# WARG_EE_Bootcamp.net
KiCad netlist of a schematic drawn in Altium Designer
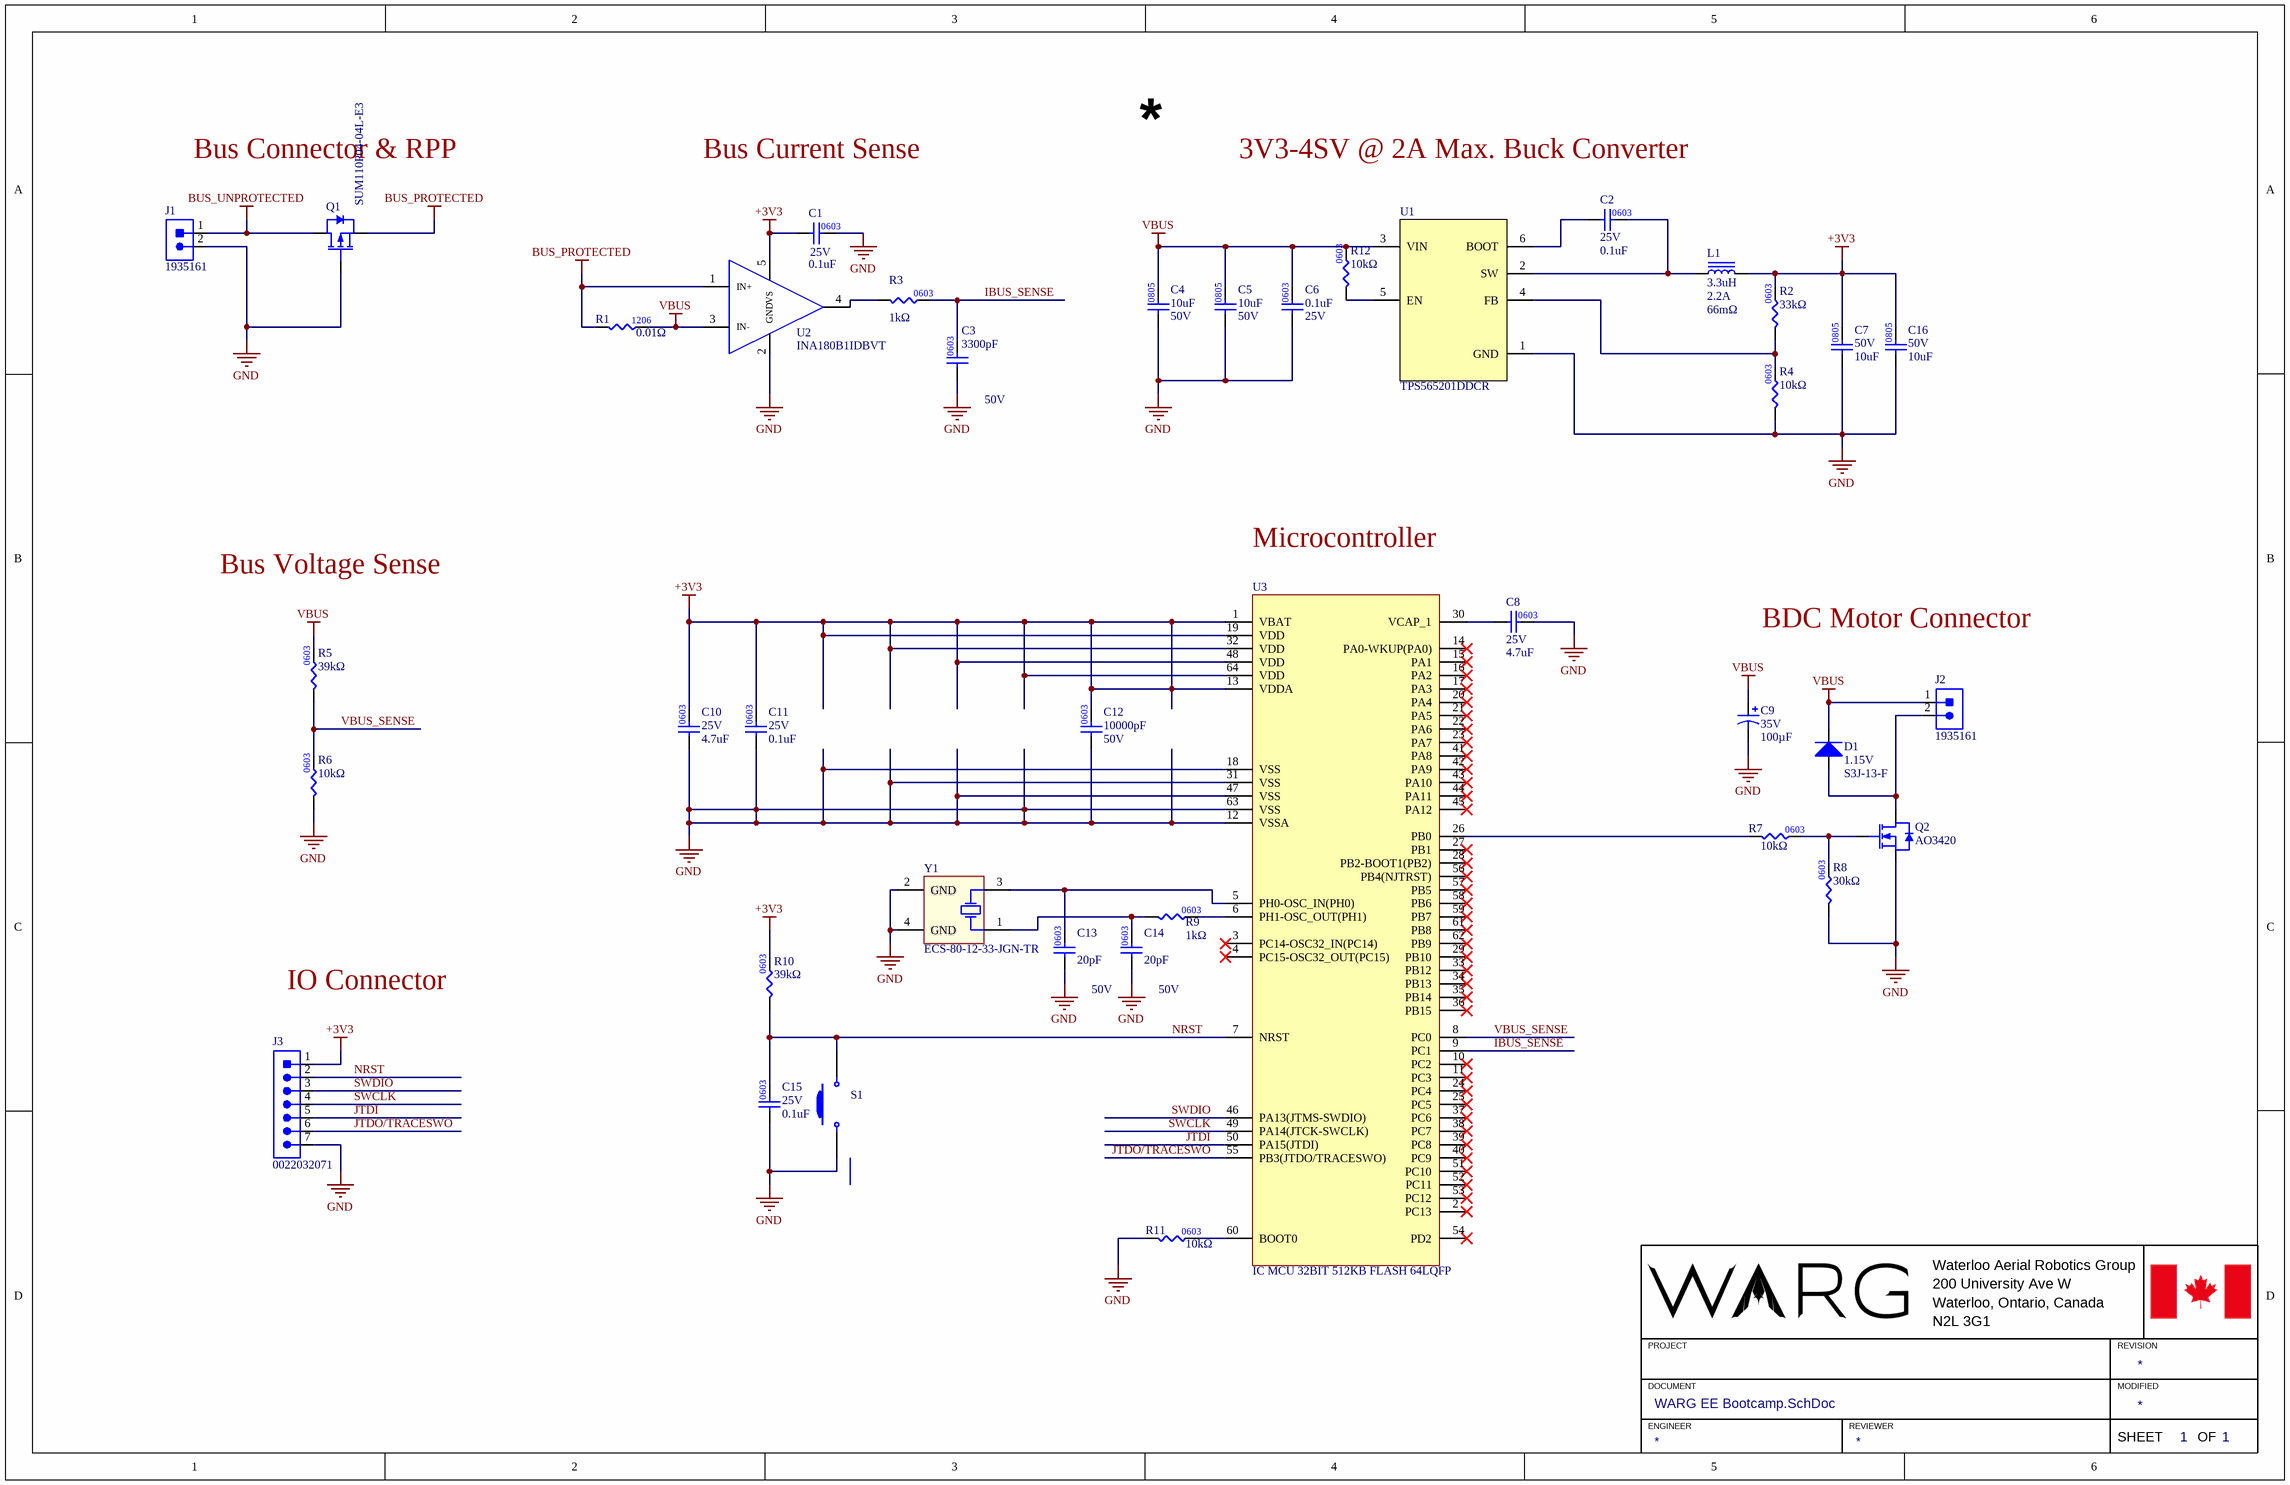
[diagram p0: WARG EE Bootcamp.SchDoc]

(export (version "E")
  (design (tool "Eeschema 10.0.6"))
  (components
    (comp (ref "C1")
      (value "0.1uF")
      (footprint "CAP0603")
      (description "CAP CER 0.1UF 25V X7R ±10% 0603")
      (fields (field (name "TOLERANCE") "±10%") (field (name "VOLTAGE") "25V"))
      (libsource (lib "Bootcamp SchLib") (part "GCM188R71E104KA57D"))
    )
    (comp (ref "C2")
      (value "0.1uF")
      (footprint "CAP0603")
      (description "CAP CER 0.1UF 25V X7R ±10% 0603")
      (fields (field (name "TOLERANCE") "±10%") (field (name "VOLTAGE") "25V"))
      (libsource (lib "Bootcamp SchLib") (part "GCM188R71E104KA57D"))
    )
    (comp (ref "C3")
      (value "3300pF")
      (footprint "CAP0603")
      (description "CAP CER 3300PF 50V C0G/NP0 0603")
      (fields (field (name "TOLERANCE") "±5%") (field (name "VOLTAGE RATING") "50V"))
      (libsource (lib "Bootcamp SchLib") (part "GRM1885C1H332JA01D"))
    )
    (comp (ref "C4")
      (value "10uF")
      (footprint "CAP0805")
      (description "CAP CER 10UF 50V X5R ±10% 0805")
      (fields (field (name "TOLERANCE") "±10%") (field (name "VOLTAGE") "50V"))
      (libsource (lib "Bootcamp SchLib") (part "GRM21BR61H106KE43L"))
    )
    (comp (ref "C5")
      (value "10uF")
      (footprint "CAP0805")
      (description "CAP CER 10UF 50V X5R ±10% 0805")
      (fields (field (name "TOLERANCE") "±10%") (field (name "VOLTAGE") "50V"))
      (libsource (lib "Bootcamp SchLib") (part "GRM21BR61H106KE43L"))
    )
    (comp (ref "C6")
      (value "0.1uF")
      (footprint "CAP0603")
      (description "CAP CER 0.1UF 25V X7R ±10% 0603")
      (fields (field (name "TOLERANCE") "±10%") (field (name "VOLTAGE") "25V"))
      (libsource (lib "Bootcamp SchLib") (part "GCM188R71E104KA57D"))
    )
    (comp (ref "C7")
      (value "10uF")
      (footprint "CAP0805")
      (description "CAP CER 10UF 50V X5R ±10% 0805")
      (fields (field (name "TOLERANCE") "±10%") (field (name "VOLTAGE") "50V"))
      (libsource (lib "Bootcamp SchLib") (part "GRM21BR61H106KE43L"))
    )
    (comp (ref "C8")
      (value "4.7uF")
      (footprint "CAP0603")
      (description "CAP CER 4.7UF 25V X6S ±10% 0603")
      (fields (field (name "TOLERANCE") "±10%") (field (name "VOLTAGE") "25V"))
      (libsource (lib "Bootcamp SchLib") (part "GRM188C81E475KE11D"))
    )
    (comp (ref "C9")
      (value "100µF")
      (footprint "RADIAL_CORNELL_D")
      (description "CAP ALUM 100UF 20% 35V SMD")
      (fields (field (name "TOLERANCE") "±20%") (field (name "VOLTAGE RATING") "35V"))
      (libsource (lib "Bootcamp SchLib") (part "35TKV100M8X10.5"))
    )
    (comp (ref "C10")
      (value "4.7uF")
      (footprint "CAP0603")
      (description "CAP CER 4.7UF 25V X6S ±10% 0603")
      (fields (field (name "TOLERANCE") "±10%") (field (name "VOLTAGE") "25V"))
      (libsource (lib "Bootcamp SchLib") (part "GRM188C81E475KE11D"))
    )
    (comp (ref "C11")
      (value "0.1uF")
      (footprint "CAP0603")
      (description "CAP CER 0.1UF 25V X7R ±10% 0603")
      (fields (field (name "TOLERANCE") "±10%") (field (name "VOLTAGE") "25V"))
      (libsource (lib "Bootcamp SchLib") (part "GCM188R71E104KA57D"))
    )
    (comp (ref "C12")
      (value "10000pF")
      (footprint "CAP0603")
      (description "CAP CER 10000PF 50V X7R 0603")
      (fields (field (name "TOLERANCE") "±5%") (field (name "VOLTAGE RATING") "50V"))
      (libsource (lib "Bootcamp SchLib") (part "C0603C103J5RAC7867"))
    )
    (comp (ref "C13")
      (value "20pF")
      (footprint "CAP0603")
      (description "CAP CER 20PF 50V C0G/NP0 0201")
      (fields (field (name "TOLERANCE") "±5%") (field (name "VOLTAGE RATING") "50V"))
      (libsource (lib "Bootcamp SchLib") (part "GRM0335C1H200GA01D"))
    )
    (comp (ref "C14")
      (value "20pF")
      (footprint "CAP0603")
      (description "CAP CER 20PF 50V C0G/NP0 0201")
      (fields (field (name "TOLERANCE") "±5%") (field (name "VOLTAGE RATING") "50V"))
      (libsource (lib "Bootcamp SchLib") (part "GRM0335C1H200GA01D"))
    )
    (comp (ref "C15")
      (value "0.1uF")
      (footprint "CAP0603")
      (description "CAP CER 0.1UF 25V X7R ±10% 0603")
      (fields (field (name "TOLERANCE") "±10%") (field (name "VOLTAGE") "25V"))
      (libsource (lib "Bootcamp SchLib") (part "GCM188R71E104KA57D"))
    )
    (comp (ref "C16")
      (value "10uF")
      (footprint "CAP0805")
      (description "CAP CER 10UF 50V X5R ±10% 0805")
      (fields (field (name "TOLERANCE") "±10%") (field (name "VOLTAGE") "50V"))
      (libsource (lib "Bootcamp SchLib") (part "GRM21BR61H106KE43L"))
    )
    (comp (ref "D1")
      (value "DIODE GEN PURP 600V 3A SMC")
      (footprint "SMC")
      (fields (field (name "FORWARD VOLTAGE") "1.15V") (field (name "MANUFACTURER PART NUMBER 1") "S3J-13-F"))
      (libsource (lib "Bootcamp SchLib") (part "S3J-FDICT-ND"))
    )
    (comp (ref "J1")
      (value "CON_2POS_SCREW_TERM")
      (footprint "1935161")
      (description "CONN SCREW TERMINAL 2X1 5MM RA TH")
      (fields (field (name "MANUFACTURER PART NUMBER 1") "1935161"))
      (libsource (lib "") (part "1935161_1"))
    )
    (comp (ref "J2")
      (value "CON_2POS_SCREW_TERM")
      (footprint "1935161")
      (description "CONN SCREW TERMINAL 2X1 5MM RA TH")
      (fields (field (name "MANUFACTURER PART NUMBER 1") "1935161"))
      (libsource (lib "Bootcamp SchLib") (part "1935161"))
    )
    (comp (ref "J3")
      (value "CONN HEADER VERT 7POS 2.54MM")
      (footprint "0022284070")
      (fields (field (name "MANUFACTURER PART NUMBER 1") "0022032071"))
      (libsource (lib "Bootcamp SchLib") (part "0022032071"))
    )
    (comp (ref "L1")
      (value "3.3uH")
      (description "FIXED IND 2.2UH 2.9A 44 MOHM SMD")
      (fields (field (name "CURRENT RATING") "2.2A") (field (name "DC RESISTANCE") "66mΩ"))
      (libsource (lib "Bootcamp SchLib") (part "SRN4018-2R2M"))
    )
    (comp (ref "Q1")
      (value "SUM110P04-04L-E3")
      (footprint "TO-263 (D²Pak)")
      (libsource (lib "Bootcamp SchLib") (part "SUM110P04-04L-E3"))
    )
    (comp (ref "Q2")
      (value "MOSFET N-CH 20V 6A SOT23-3L")
      (footprint "SOT23-3")
      (fields (field (name "MANUFACTURER PART NUMBER 1") "AO3420"))
      (libsource (lib "Bootcamp SchLib") (part "AO3420"))
    )
    (comp (ref "R1")
      (value "0.01Ω")
      (footprint "RES1206")
      (description "RES 0.01 OHM 1% 1/4W 1206")
      (fields (field (name "TOLERANCE") "±1%"))
      (libsource (lib "Bootcamp SchLib") (part "PF1206FRF070R01L"))
    )
    (comp (ref "R2")
      (value "33kΩ")
      (footprint "RES0603")
      (description "RES 33K OHM 1% 1/10W 0603")
      (fields (field (name "TOLERANCE") "±1%"))
      (libsource (lib "Bootcamp SchLib") (part "RC0603FR-0733KL"))
    )
    (comp (ref "R3")
      (value "1kΩ")
      (footprint "RES0603")
      (description "RES 1K OHM 1% 1/10W 0603")
      (fields (field (name "TOLERANCE") "±1%"))
      (libsource (lib "Bootcamp SchLib") (part "RC0603FR-071KL"))
    )
    (comp (ref "R4")
      (value "10kΩ")
      (footprint "RES0603")
      (description "RES 10K OHM 1% 1/10W 0603")
      (fields (field (name "TOLERANCE") "±1%"))
      (libsource (lib "Bootcamp SchLib") (part "RC0603FR-0710KL"))
    )
    (comp (ref "R5")
      (value "39kΩ")
      (footprint "RES0603")
      (description "RES 39K OHM 1% 1/10W 0603")
      (fields (field (name "TOLERANCE") "±1%"))
      (libsource (lib "Bootcamp SchLib") (part "RC0603FR-0739KL"))
    )
    (comp (ref "R6")
      (value "10kΩ")
      (footprint "RES0603")
      (description "RES 10K OHM 1% 1/10W 0603")
      (fields (field (name "TOLERANCE") "±1%"))
      (libsource (lib "Bootcamp SchLib") (part "RC0603FR-0710KL"))
    )
    (comp (ref "R7")
      (value "10kΩ")
      (footprint "RES0603")
      (description "RES 10K OHM 1% 1/10W 0603")
      (fields (field (name "TOLERANCE") "±1%"))
      (libsource (lib "Bootcamp SchLib") (part "RC0603FR-0710KL"))
    )
    (comp (ref "R8")
      (value "30kΩ")
      (footprint "RES0603")
      (description "RES 30K OHM 1% 1/10W 0603")
      (fields (field (name "TOLERANCE") "±1%"))
      (libsource (lib "Bootcamp SchLib") (part "RC0603FR-0730KL"))
    )
    (comp (ref "R9")
      (value "1kΩ")
      (footprint "RES0603")
      (description "RES 1K OHM 1% 1/10W 0603")
      (fields (field (name "TOLERANCE") "±1%"))
      (libsource (lib "Bootcamp SchLib") (part "RC0603FR-071KL"))
    )
    (comp (ref "R10")
      (value "39kΩ")
      (footprint "RES0603")
      (description "RES 39K OHM 1% 1/10W 0603")
      (fields (field (name "TOLERANCE") "±1%"))
      (libsource (lib "Bootcamp SchLib") (part "RC0603FR-0739KL"))
    )
    (comp (ref "R11")
      (value "10kΩ")
      (footprint "RES0603")
      (description "RES 10K OHM 1% 1/10W 0603")
      (fields (field (name "TOLERANCE") "±1%"))
      (libsource (lib "Bootcamp SchLib") (part "RC0603FR-0710KL"))
    )
    (comp (ref "R12")
      (value "10kΩ")
      (footprint "RES0603")
      (description "RES 10K OHM 1% 1/10W 0603")
      (fields (field (name "TOLERANCE") "±1%"))
      (libsource (lib "Bootcamp SchLib") (part "RC0603FR-0710KL"))
    )
    (comp (ref "S1")
      (value "435151014824")
      (footprint "435151014824")
      (description "SMT 3.0 X 2.6 MM TACT SWITCH WIT")
      (libsource (lib "Bootcamp SchLib") (part "435151014824"))
    )
    (comp (ref "U1")
      (value "IC REG BUCK ADJ 5A TSOT23-6")
      (footprint "SOT23-6")
      (fields (field (name "MANUFACTURER PART NUMBER 1") "TPS565201DDCR"))
      (libsource (lib "Bootcamp SchLib") (part "TPS565201DDCR"))
    )
    (comp (ref "U2")
      (value "IC CURR SENSE 1 CIRCUIT SOT23-5")
      (footprint "SOT23-5")
      (fields (field (name "MANUFACTURER PART NUMBER 1") "INA180B1IDBVT"))
      (libsource (lib "Bootcamp SchLib") (part "INA180B1IDBVT"))
    )
    (comp (ref "U3")
      (value "IC MCU 32BIT 512KB FLASH 64LQFP")
      (footprint "STM_LQFP64_N")
      (libsource (lib "Bootcamp SchLib") (part "STM32F446RET6"))
    )
    (comp (ref "Y1")
      (value "CRYSTAL 8MHZ 12PF SMD")
      (description "8 MHz ±20ppm Crystal 12pF 400 Ohms 4-SMD")
      (fields (field (name "MANUFACTURER PART NUMBER 1") "ECS-80-12-33-JGN-TR"))
      (libsource (lib "Bootcamp SchLib") (part "ECS-80-12-33-JGN-TR"))
    )
  )
  (nets
    (net (code "1") (name "+3V3") (class "Default")
      (node (ref "C1") (pin "1") (pinfunction "1_1") (pintype "passive"))
      (node (ref "C10") (pin "2") (pinfunction "2_2") (pintype "passive"))
      (node (ref "C11") (pin "2") (pinfunction "2_2") (pintype "passive"))
      (node (ref "C12") (pin "2") (pinfunction "2_2") (pintype "passive"))
      (node (ref "C16") (pin "2") (pinfunction "2_2") (pintype "passive"))
      (node (ref "C7") (pin "2") (pinfunction "2_2") (pintype "passive"))
      (node (ref "J3") (pin "1") (pinfunction "1_1") (pintype "passive"))
      (node (ref "L1") (pin "2") (pinfunction "2_2") (pintype "passive"))
      (node (ref "R10") (pin "2") (pinfunction "2_2") (pintype "passive"))
      (node (ref "R2") (pin "2") (pinfunction "2_2") (pintype "passive"))
      (node (ref "U2") (pin "5") (pinfunction "VS_5") (pintype "power_in"))
      (node (ref "U3") (pin "1") (pinfunction "VBAT_1") (pintype "passive"))
      (node (ref "U3") (pin "13") (pinfunction "VDDA_13") (pintype "passive"))
      (node (ref "U3") (pin "19") (pinfunction "VDD_19") (pintype "passive"))
      (node (ref "U3") (pin "32") (pinfunction "VDD_32") (pintype "passive"))
      (node (ref "U3") (pin "48") (pinfunction "VDD_48") (pintype "passive"))
      (node (ref "U3") (pin "64") (pinfunction "VDD_64") (pintype "passive"))
    )
    (net (code "2") (name "/IBUS_SENSE") (class "Default")
      (node (ref "C3") (pin "2") (pinfunction "2_2") (pintype "passive"))
      (node (ref "R3") (pin "2") (pinfunction "2_2") (pintype "passive"))
      (node (ref "U3") (pin "9") (pinfunction "PC1_9") (pintype "passive"))
    )
    (net (code "3") (name "/JTDI") (class "Default")
      (node (ref "J3") (pin "5") (pinfunction "5_5") (pintype "passive"))
      (node (ref "U3") (pin "50") (pinfunction "PA15(JTDI)_50") (pintype "passive"))
    )
    (net (code "4") (name "/JTDO{slash}TRACESWO") (class "Default")
      (node (ref "J3") (pin "6") (pinfunction "6_6") (pintype "passive"))
      (node (ref "U3") (pin "55") (pinfunction "PB3(JTDO/TRACESWO)_55") (pintype "passive"))
    )
    (net (code "5") (name "/NRST") (class "Default")
      (node (ref "C15") (pin "2") (pinfunction "2_2") (pintype "passive"))
      (node (ref "J3") (pin "2") (pinfunction "2_2") (pintype "passive"))
      (node (ref "R10") (pin "1") (pinfunction "1_1") (pintype "passive"))
      (node (ref "S1") (pin "2") (pintype "passive"))
      (node (ref "U3") (pin "7") (pinfunction "NRST_7") (pintype "passive"))
    )
    (net (code "6") (name "/SWCLK") (class "Default")
      (node (ref "J3") (pin "4") (pinfunction "4_4") (pintype "passive"))
      (node (ref "U3") (pin "49") (pinfunction "PA14(JTCK-SWCLK)_49") (pintype "passive"))
    )
    (net (code "7") (name "/SWDIO") (class "Default")
      (node (ref "J3") (pin "3") (pinfunction "3_3") (pintype "passive"))
      (node (ref "U3") (pin "46") (pinfunction "PA13(JTMS-SWDIO)_46") (pintype "passive"))
    )
    (net (code "8") (name "/VBUS_SENSE") (class "Default")
      (node (ref "R5") (pin "1") (pinfunction "1_1") (pintype "passive"))
      (node (ref "R6") (pin "2") (pinfunction "2_2") (pintype "passive"))
      (node (ref "U3") (pin "8") (pinfunction "PC0_8") (pintype "passive"))
    )
    (net (code "9") (name "BUS_PROTECTED") (class "Default")
      (node (ref "Q1") (pin "1") (pinfunction "Source_1") (pintype "passive"))
      (node (ref "R1") (pin "1") (pinfunction "1_1") (pintype "passive"))
      (node (ref "U2") (pin "1") (pinfunction "IN+_1") (pintype "passive"))
    )
    (net (code "10") (name "BUS_UNPROTECTED") (class "Default")
      (node (ref "J1") (pin "1") (pinfunction "1_1") (pintype "passive"))
      (node (ref "Q1") (pin "3") (pinfunction "Drain_3") (pintype "passive"))
    )
    (net (code "11") (name "GND") (class "Default")
      (node (ref "C1") (pin "2") (pinfunction "2_2") (pintype "passive"))
      (node (ref "C10") (pin "1") (pinfunction "1_1") (pintype "passive"))
      (node (ref "C11") (pin "1") (pinfunction "1_1") (pintype "passive"))
      (node (ref "C12") (pin "1") (pinfunction "1_1") (pintype "passive"))
      (node (ref "C13") (pin "1") (pinfunction "1_1") (pintype "passive"))
      (node (ref "C14") (pin "1") (pinfunction "1_1") (pintype "passive"))
      (node (ref "C15") (pin "1") (pinfunction "1_1") (pintype "passive"))
      (node (ref "C16") (pin "1") (pinfunction "1_1") (pintype "passive"))
      (node (ref "C3") (pin "1") (pinfunction "1_1") (pintype "passive"))
      (node (ref "C4") (pin "1") (pinfunction "1_1") (pintype "passive"))
      (node (ref "C5") (pin "1") (pinfunction "1_1") (pintype "passive"))
      (node (ref "C6") (pin "1") (pinfunction "1_1") (pintype "passive"))
      (node (ref "C7") (pin "1") (pinfunction "1_1") (pintype "passive"))
      (node (ref "C8") (pin "2") (pinfunction "2_2") (pintype "passive"))
      (node (ref "C9") (pin "2") (pinfunction "2_2") (pintype "passive"))
      (node (ref "J1") (pin "2") (pinfunction "2_2") (pintype "passive"))
      (node (ref "J3") (pin "7") (pinfunction "7_7") (pintype "passive"))
      (node (ref "Q1") (pin "2") (pinfunction "Gate_2") (pintype "passive"))
      (node (ref "Q2") (pin "1") (pinfunction "Source_1") (pintype "passive"))
      (node (ref "R11") (pin "1") (pinfunction "1_1") (pintype "passive"))
      (node (ref "R4") (pin "1") (pinfunction "1_1") (pintype "passive"))
      (node (ref "R6") (pin "1") (pinfunction "1_1") (pintype "passive"))
      (node (ref "R8") (pin "1") (pinfunction "1_1") (pintype "passive"))
      (node (ref "S1") (pin "1") (pintype "passive"))
      (node (ref "U1") (pin "1") (pinfunction "GND_1") (pintype "passive"))
      (node (ref "U2") (pin "2") (pinfunction "GND_2") (pintype "passive"))
      (node (ref "U3") (pin "12") (pinfunction "VSSA_12") (pintype "passive"))
      (node (ref "U3") (pin "18") (pinfunction "VSS_18") (pintype "passive"))
      (node (ref "U3") (pin "31") (pinfunction "VSS_31") (pintype "passive"))
      (node (ref "U3") (pin "47") (pinfunction "VSS_47") (pintype "passive"))
      (node (ref "U3") (pin "63") (pinfunction "VSS_63") (pintype "passive"))
      (node (ref "Y1") (pin "2") (pinfunction "GND_2") (pintype "power_in"))
      (node (ref "Y1") (pin "4") (pinfunction "GND_4") (pintype "passive"))
    )
    (net (code "12") (name "Net-(D1-A)") (class "Default")
      (node (ref "D1") (pin "1") (pinfunction "A_1") (pintype "passive"))
      (node (ref "J2") (pin "2") (pinfunction "2_2") (pintype "passive"))
      (node (ref "Q2") (pin "3") (pinfunction "Drain_3") (pintype "passive"))
    )
    (net (code "13") (name "Net-(Q2-Gate)") (class "Default")
      (node (ref "Q2") (pin "2") (pinfunction "Gate_2") (pintype "passive"))
      (node (ref "R7") (pin "2") (pinfunction "2_2") (pintype "passive"))
      (node (ref "R8") (pin "2") (pinfunction "2_2") (pintype "passive"))
    )
    (net (code "14") (name "Net-(U1-BOOT)") (class "Default")
      (node (ref "C2") (pin "1") (pinfunction "1_1") (pintype "passive"))
      (node (ref "U1") (pin "6") (pinfunction "BOOT_6") (pintype "passive"))
    )
    (net (code "15") (name "Net-(U1-EN)") (class "Default")
      (node (ref "R12") (pin "1") (pinfunction "1_1") (pintype "passive"))
      (node (ref "U1") (pin "5") (pinfunction "EN_5") (pintype "passive"))
    )
    (net (code "16") (name "Net-(U1-FB)") (class "Default")
      (node (ref "R2") (pin "1") (pinfunction "1_1") (pintype "passive"))
      (node (ref "R4") (pin "2") (pinfunction "2_2") (pintype "passive"))
      (node (ref "U1") (pin "4") (pinfunction "FB_4") (pintype "passive"))
    )
    (net (code "17") (name "Net-(U1-SW)") (class "Default")
      (node (ref "C2") (pin "2") (pinfunction "2_2") (pintype "passive"))
      (node (ref "L1") (pin "1") (pinfunction "1_1") (pintype "passive"))
      (node (ref "U1") (pin "2") (pinfunction "SW_2") (pintype "passive"))
    )
    (net (code "18") (name "Net-(U2-OUT)") (class "Default")
      (node (ref "R3") (pin "1") (pinfunction "1_1") (pintype "passive"))
      (node (ref "U2") (pin "4") (pinfunction "OUT_4") (pintype "passive"))
    )
    (net (code "19") (name "Net-(U3-BOOT0)") (class "Default")
      (node (ref "R11") (pin "2") (pinfunction "2_2") (pintype "passive"))
      (node (ref "U3") (pin "60") (pinfunction "BOOT0_60") (pintype "passive"))
    )
    (net (code "20") (name "Net-(U3-PB0)") (class "Default")
      (node (ref "R7") (pin "1") (pinfunction "1_1") (pintype "passive"))
      (node (ref "U3") (pin "26") (pinfunction "PB0_26") (pintype "passive"))
    )
    (net (code "21") (name "Net-(U3-PH0-OSC_IN(PH0))") (class "Default")
      (node (ref "C13") (pin "2") (pinfunction "2_2") (pintype "passive"))
      (node (ref "U3") (pin "5") (pinfunction "PH0-OSC_IN(PH0)_5") (pintype "passive"))
      (node (ref "Y1") (pin "3") (pinfunction "OUT/IN_3") (pintype "passive"))
    )
    (net (code "22") (name "Net-(U3-PH1-OSC_OUT(PH1))") (class "Default")
      (node (ref "R9") (pin "2") (pinfunction "2_2") (pintype "passive"))
      (node (ref "U3") (pin "6") (pinfunction "PH1-OSC_OUT(PH1)_6") (pintype "passive"))
    )
    (net (code "23") (name "Net-(U3-VCAP_1)") (class "Default")
      (node (ref "C8") (pin "1") (pinfunction "1_1") (pintype "passive"))
      (node (ref "U3") (pin "30") (pinfunction "VCAP_1_30") (pintype "passive"))
    )
    (net (code "24") (name "Net-(Y1-IN{slash}OUT)") (class "Default")
      (node (ref "C14") (pin "2") (pinfunction "2_2") (pintype "passive"))
      (node (ref "R9") (pin "1") (pinfunction "1_1") (pintype "passive"))
      (node (ref "Y1") (pin "1") (pinfunction "IN/OUT_1") (pintype "passive"))
    )
    (net (code "25") (name "VBUS") (class "Default")
      (node (ref "C4") (pin "2") (pinfunction "2_2") (pintype "passive"))
      (node (ref "C5") (pin "2") (pinfunction "2_2") (pintype "passive"))
      (node (ref "C6") (pin "2") (pinfunction "2_2") (pintype "passive"))
      (node (ref "C9") (pin "1") (pinfunction "1_1") (pintype "passive"))
      (node (ref "D1") (pin "2") (pinfunction "K_2") (pintype "passive"))
      (node (ref "J2") (pin "1") (pinfunction "1_1") (pintype "passive"))
      (node (ref "R1") (pin "2") (pinfunction "2_2") (pintype "passive"))
      (node (ref "R12") (pin "2") (pinfunction "2_2") (pintype "passive"))
      (node (ref "R5") (pin "2") (pinfunction "2_2") (pintype "passive"))
      (node (ref "U1") (pin "3") (pinfunction "VIN_3") (pintype "passive"))
      (node (ref "U2") (pin "3") (pinfunction "IN-_3") (pintype "passive"))
    )
    (net (code "26") (name "unconnected-(U3-PA0-WKUP(PA0)-Pad14)") (class "Default")
      (node (ref "U3") (pin "14") (pinfunction "PA0-WKUP(PA0)_14") (pintype "passive+no_connect"))
    )
    (net (code "27") (name "unconnected-(U3-PA1-Pad15)") (class "Default")
      (node (ref "U3") (pin "15") (pinfunction "PA1_15") (pintype "passive+no_connect"))
    )
    (net (code "28") (name "unconnected-(U3-PA2-Pad16)") (class "Default")
      (node (ref "U3") (pin "16") (pinfunction "PA2_16") (pintype "passive+no_connect"))
    )
    (net (code "29") (name "unconnected-(U3-PA3-Pad17)") (class "Default")
      (node (ref "U3") (pin "17") (pinfunction "PA3_17") (pintype "passive+no_connect"))
    )
    (net (code "30") (name "unconnected-(U3-PA4-Pad20)") (class "Default")
      (node (ref "U3") (pin "20") (pinfunction "PA4_20") (pintype "passive+no_connect"))
    )
    (net (code "31") (name "unconnected-(U3-PA5-Pad21)") (class "Default")
      (node (ref "U3") (pin "21") (pinfunction "PA5_21") (pintype "passive+no_connect"))
    )
    (net (code "32") (name "unconnected-(U3-PA6-Pad22)") (class "Default")
      (node (ref "U3") (pin "22") (pinfunction "PA6_22") (pintype "passive+no_connect"))
    )
    (net (code "33") (name "unconnected-(U3-PA7-Pad23)") (class "Default")
      (node (ref "U3") (pin "23") (pinfunction "PA7_23") (pintype "passive+no_connect"))
    )
    (net (code "34") (name "unconnected-(U3-PA8-Pad41)") (class "Default")
      (node (ref "U3") (pin "41") (pinfunction "PA8_41") (pintype "passive+no_connect"))
    )
    (net (code "35") (name "unconnected-(U3-PA9-Pad42)") (class "Default")
      (node (ref "U3") (pin "42") (pinfunction "PA9_42") (pintype "passive+no_connect"))
    )
    (net (code "36") (name "unconnected-(U3-PA10-Pad43)") (class "Default")
      (node (ref "U3") (pin "43") (pinfunction "PA10_43") (pintype "passive+no_connect"))
    )
    (net (code "37") (name "unconnected-(U3-PA11-Pad44)") (class "Default")
      (node (ref "U3") (pin "44") (pinfunction "PA11_44") (pintype "passive+no_connect"))
    )
    (net (code "38") (name "unconnected-(U3-PA12-Pad45)") (class "Default")
      (node (ref "U3") (pin "45") (pinfunction "PA12_45") (pintype "passive+no_connect"))
    )
    (net (code "39") (name "unconnected-(U3-PB1-Pad27)") (class "Default")
      (node (ref "U3") (pin "27") (pinfunction "PB1_27") (pintype "passive+no_connect"))
    )
    (net (code "40") (name "unconnected-(U3-PB2-BOOT1(PB2)-Pad28)") (class "Default")
      (node (ref "U3") (pin "28") (pinfunction "PB2-BOOT1(PB2)_28") (pintype "passive+no_connect"))
    )
    (net (code "41") (name "unconnected-(U3-PB4(NJTRST)-Pad56)") (class "Default")
      (node (ref "U3") (pin "56") (pinfunction "PB4(NJTRST)_56") (pintype "passive+no_connect"))
    )
    (net (code "42") (name "unconnected-(U3-PB5-Pad57)") (class "Default")
      (node (ref "U3") (pin "57") (pinfunction "PB5_57") (pintype "passive+no_connect"))
    )
    (net (code "43") (name "unconnected-(U3-PB6-Pad58)") (class "Default")
      (node (ref "U3") (pin "58") (pinfunction "PB6_58") (pintype "passive+no_connect"))
    )
    (net (code "44") (name "unconnected-(U3-PB7-Pad59)") (class "Default")
      (node (ref "U3") (pin "59") (pinfunction "PB7_59") (pintype "passive+no_connect"))
    )
    (net (code "45") (name "unconnected-(U3-PB8-Pad61)") (class "Default")
      (node (ref "U3") (pin "61") (pinfunction "PB8_61") (pintype "passive+no_connect"))
    )
    (net (code "46") (name "unconnected-(U3-PB9-Pad62)") (class "Default")
      (node (ref "U3") (pin "62") (pinfunction "PB9_62") (pintype "passive+no_connect"))
    )
    (net (code "47") (name "unconnected-(U3-PB10-Pad29)") (class "Default")
      (node (ref "U3") (pin "29") (pinfunction "PB10_29") (pintype "passive+no_connect"))
    )
    (net (code "48") (name "unconnected-(U3-PB12-Pad33)") (class "Default")
      (node (ref "U3") (pin "33") (pinfunction "PB12_33") (pintype "passive+no_connect"))
    )
    (net (code "49") (name "unconnected-(U3-PB13-Pad34)") (class "Default")
      (node (ref "U3") (pin "34") (pinfunction "PB13_34") (pintype "passive+no_connect"))
    )
    (net (code "50") (name "unconnected-(U3-PB14-Pad35)") (class "Default")
      (node (ref "U3") (pin "35") (pinfunction "PB14_35") (pintype "passive+no_connect"))
    )
    (net (code "51") (name "unconnected-(U3-PB15-Pad36)") (class "Default")
      (node (ref "U3") (pin "36") (pinfunction "PB15_36") (pintype "passive+no_connect"))
    )
    (net (code "52") (name "unconnected-(U3-PC2-Pad10)") (class "Default")
      (node (ref "U3") (pin "10") (pinfunction "PC2_10") (pintype "passive+no_connect"))
    )
    (net (code "53") (name "unconnected-(U3-PC3-Pad11)") (class "Default")
      (node (ref "U3") (pin "11") (pinfunction "PC3_11") (pintype "passive+no_connect"))
    )
    (net (code "54") (name "unconnected-(U3-PC4-Pad24)") (class "Default")
      (node (ref "U3") (pin "24") (pinfunction "PC4_24") (pintype "passive+no_connect"))
    )
    (net (code "55") (name "unconnected-(U3-PC5-Pad25)") (class "Default")
      (node (ref "U3") (pin "25") (pinfunction "PC5_25") (pintype "passive+no_connect"))
    )
    (net (code "56") (name "unconnected-(U3-PC6-Pad37)") (class "Default")
      (node (ref "U3") (pin "37") (pinfunction "PC6_37") (pintype "passive+no_connect"))
    )
    (net (code "57") (name "unconnected-(U3-PC7-Pad38)") (class "Default")
      (node (ref "U3") (pin "38") (pinfunction "PC7_38") (pintype "passive+no_connect"))
    )
    (net (code "58") (name "unconnected-(U3-PC8-Pad39)") (class "Default")
      (node (ref "U3") (pin "39") (pinfunction "PC8_39") (pintype "passive+no_connect"))
    )
    (net (code "59") (name "unconnected-(U3-PC9-Pad40)") (class "Default")
      (node (ref "U3") (pin "40") (pinfunction "PC9_40") (pintype "passive+no_connect"))
    )
    (net (code "60") (name "unconnected-(U3-PC10-Pad51)") (class "Default")
      (node (ref "U3") (pin "51") (pinfunction "PC10_51") (pintype "passive+no_connect"))
    )
    (net (code "61") (name "unconnected-(U3-PC11-Pad52)") (class "Default")
      (node (ref "U3") (pin "52") (pinfunction "PC11_52") (pintype "passive+no_connect"))
    )
    (net (code "62") (name "unconnected-(U3-PC12-Pad53)") (class "Default")
      (node (ref "U3") (pin "53") (pinfunction "PC12_53") (pintype "passive+no_connect"))
    )
    (net (code "63") (name "unconnected-(U3-PC13-Pad2)") (class "Default")
      (node (ref "U3") (pin "2") (pinfunction "PC13_2") (pintype "passive+no_connect"))
    )
    (net (code "64") (name "unconnected-(U3-PC14-OSC32_IN(PC14)-Pad3)") (class "Default")
      (node (ref "U3") (pin "3") (pinfunction "PC14-OSC32_IN(PC14)_3") (pintype "passive+no_connect"))
    )
    (net (code "65") (name "unconnected-(U3-PC15-OSC32_OUT(PC15)-Pad4)") (class "Default")
      (node (ref "U3") (pin "4") (pinfunction "PC15-OSC32_OUT(PC15)_4") (pintype "passive+no_connect"))
    )
    (net (code "66") (name "unconnected-(U3-PD2-Pad54)") (class "Default")
      (node (ref "U3") (pin "54") (pinfunction "PD2_54") (pintype "passive+no_connect"))
    )
  )
)
